# Connectors.net
KiCad netlist of a schematic drawn in Altium Designer
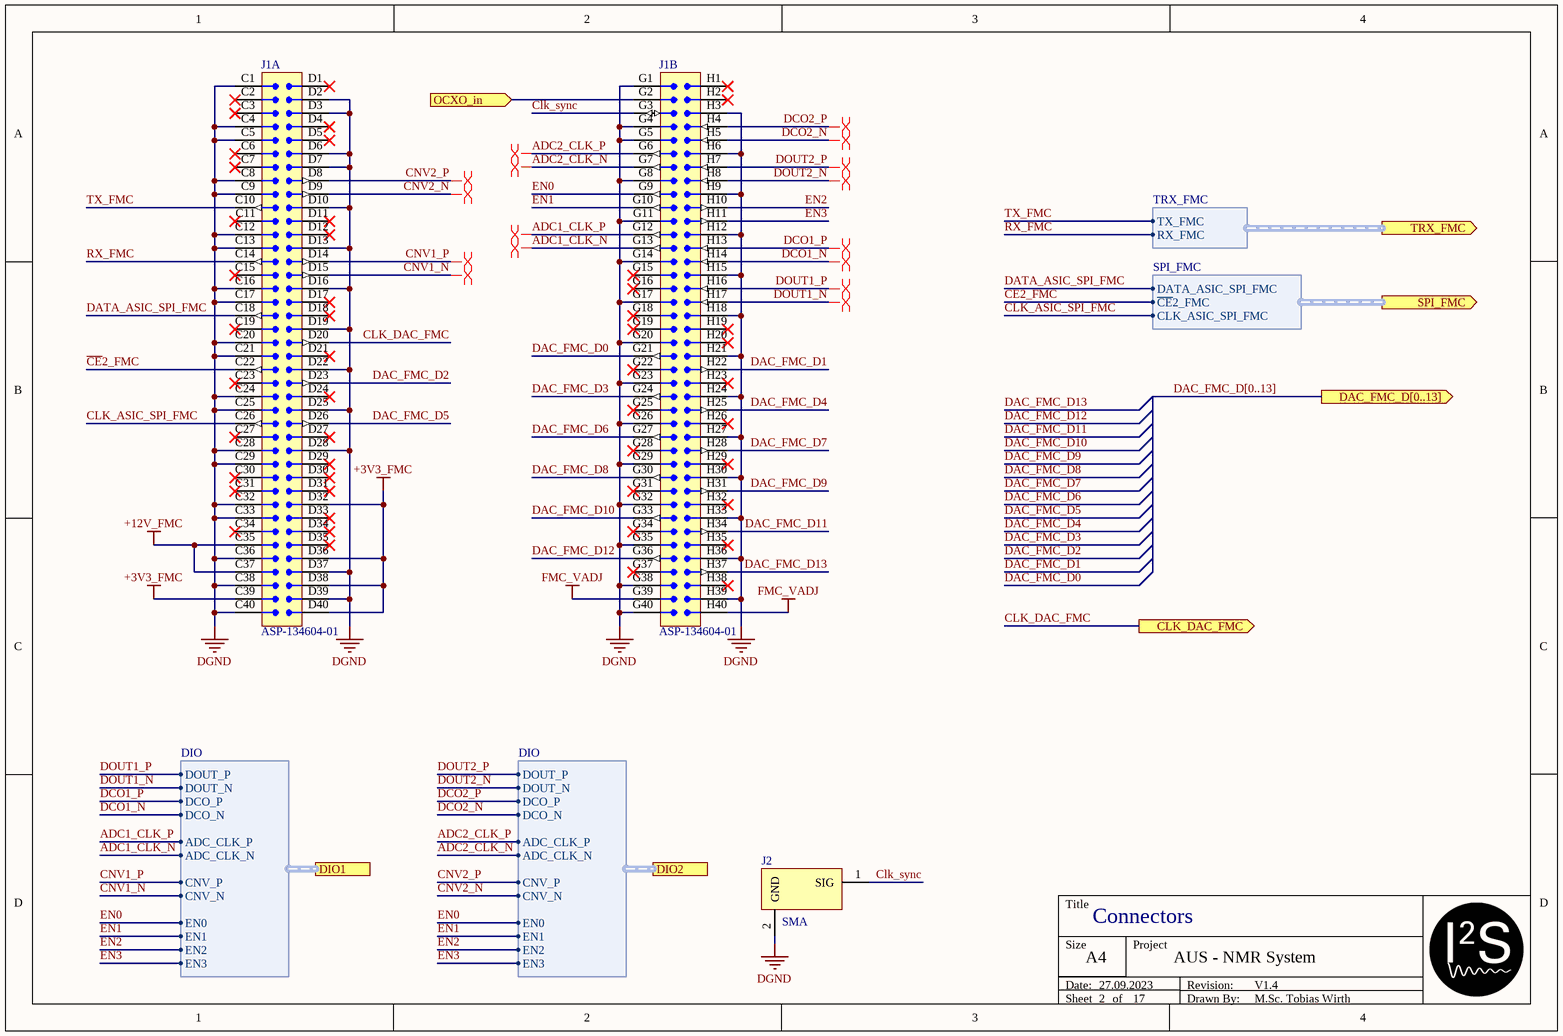
[diagram p0: Connectors.SchDoc]

(export (version "E")
  (design (tool "Eeschema 10.0.6"))
  (components
    (comp (ref "J1")
      (value "ASP-134604-01")
      (footprint "ASP13460401")
      (description "Board to Board & Mezzanine Connectors \"ASP\"")
      (libsource (lib "IIS-Lib_TW") (part "ASP-134604-01"))
    )
    (comp (ref "J2") (value "SMA") (footprint "SMA") (libsource (lib "IIS-Lib_TW") (part "SMA")))
  )
  (nets
    (net (code "4") (name "+3V3_FMC") (class "Default")
      (node (ref "J1") (pin "C39") (pinfunction "C39_C39") (pintype "passive"))
      (node (ref "J1") (pin "D32") (pinfunction "D32_D32") (pintype "passive"))
      (node (ref "J1") (pin "D36") (pinfunction "D36_D36") (pintype "passive"))
      (node (ref "J1") (pin "D38") (pinfunction "D38_D38") (pintype "passive"))
      (node (ref "J1") (pin "D40") (pinfunction "D40_D40") (pintype "passive"))
    )
    (net (code "5") (name "+12V_FMC") (class "Default")
      (node (ref "J1") (pin "C35") (pinfunction "C35_C35") (pintype "passive"))
      (node (ref "J1") (pin "C37") (pinfunction "C37_C37") (pintype "passive"))
    )
    (net (code "6") (name "/ADC1_CLK_N") (class "Default")
      (node (ref "J1") (pin "G13") (pinfunction "G13_G13") (pintype "output"))
    )
    (net (code "7") (name "/ADC1_CLK_P") (class "Default")
      (node (ref "J1") (pin "G12") (pinfunction "G12_G12") (pintype "output"))
    )
    (net (code "8") (name "/ADC2_CLK_N") (class "Default")
      (node (ref "J1") (pin "G7") (pinfunction "G7_G7") (pintype "output"))
    )
    (net (code "9") (name "/ADC2_CLK_P") (class "Default")
      (node (ref "J1") (pin "G6") (pinfunction "G6_G6") (pintype "output"))
    )
    (net (code "10") (name "/CLK_ASIC_SPI_FMC") (class "Default")
      (node (ref "J1") (pin "C26") (pinfunction "C26_C26") (pintype "passive"))
    )
    (net (code "11") (name "/CLK_DAC_FMC") (class "Default")
      (node (ref "J1") (pin "D20") (pinfunction "D20_D20") (pintype "passive"))
    )
    (net (code "12") (name "/CNV1_N") (class "Default")
      (node (ref "J1") (pin "D15") (pinfunction "D15_D15") (pintype "passive"))
    )
    (net (code "13") (name "/CNV1_P") (class "Default")
      (node (ref "J1") (pin "D14") (pinfunction "D14_D14") (pintype "passive"))
    )
    (net (code "14") (name "/CNV2_N") (class "Default")
      (node (ref "J1") (pin "D9") (pinfunction "D9_D9") (pintype "passive"))
    )
    (net (code "15") (name "/CNV2_P") (class "Default")
      (node (ref "J1") (pin "D8") (pinfunction "D8_D8") (pintype "passive"))
    )
    (net (code "16") (name "/Clk_sync") (class "Default")
      (node (ref "J1") (pin "G3") (pinfunction "G3_G3") (pintype "bidirectional"))
      (node (ref "J2") (pin "1") (pinfunction "SIG_1") (pintype "passive"))
    )
    (net (code "17") (name "/DAC_FMC_D0") (class "Default")
      (node (ref "J1") (pin "G21") (pinfunction "G21_G21") (pintype "output"))
    )
    (net (code "18") (name "/DAC_FMC_D1") (class "Default")
      (node (ref "J1") (pin "H22") (pinfunction "H22_H22") (pintype "output"))
    )
    (net (code "19") (name "/DAC_FMC_D2") (class "Default")
      (node (ref "J1") (pin "D23") (pinfunction "D23_D23") (pintype "passive"))
    )
    (net (code "20") (name "/DAC_FMC_D3") (class "Default")
      (node (ref "J1") (pin "G24") (pinfunction "G24_G24") (pintype "output"))
    )
    (net (code "21") (name "/DAC_FMC_D4") (class "Default")
      (node (ref "J1") (pin "H25") (pinfunction "H25_H25") (pintype "output"))
    )
    (net (code "22") (name "/DAC_FMC_D5") (class "Default")
      (node (ref "J1") (pin "D26") (pinfunction "D26_D26") (pintype "passive"))
    )
    (net (code "23") (name "/DAC_FMC_D6") (class "Default")
      (node (ref "J1") (pin "G27") (pinfunction "G27_G27") (pintype "output"))
    )
    (net (code "24") (name "/DAC_FMC_D7") (class "Default")
      (node (ref "J1") (pin "H28") (pinfunction "H28_H28") (pintype "output"))
    )
    (net (code "25") (name "/DAC_FMC_D8") (class "Default")
      (node (ref "J1") (pin "G30") (pinfunction "G30_G30") (pintype "output"))
    )
    (net (code "26") (name "/DAC_FMC_D9") (class "Default")
      (node (ref "J1") (pin "H31") (pinfunction "H31_H31") (pintype "output"))
    )
    (net (code "27") (name "/DAC_FMC_D10") (class "Default")
      (node (ref "J1") (pin "G33") (pinfunction "G33_G33") (pintype "output"))
    )
    (net (code "28") (name "/DAC_FMC_D11") (class "Default")
      (node (ref "J1") (pin "H34") (pinfunction "H34_H34") (pintype "output"))
    )
    (net (code "29") (name "/DAC_FMC_D12") (class "Default")
      (node (ref "J1") (pin "G36") (pinfunction "G36_G36") (pintype "output"))
    )
    (net (code "30") (name "/DAC_FMC_D13") (class "Default")
      (node (ref "J1") (pin "H37") (pinfunction "H37_H37") (pintype "output"))
    )
    (net (code "32") (name "/DATA_ASIC_SPI_FMC") (class "Default")
      (node (ref "J1") (pin "C18") (pinfunction "C18_C18") (pintype "passive"))
    )
    (net (code "33") (name "/DCO1_N") (class "Default")
      (node (ref "J1") (pin "H14") (pinfunction "H14_H14") (pintype "input"))
    )
    (net (code "34") (name "/DCO1_P") (class "Default")
      (node (ref "J1") (pin "H13") (pinfunction "H13_H13") (pintype "input"))
    )
    (net (code "35") (name "/DCO2_N") (class "Default")
      (node (ref "J1") (pin "H5") (pinfunction "H5_H5") (pintype "input"))
    )
    (net (code "36") (name "/DCO2_P") (class "Default")
      (node (ref "J1") (pin "H4") (pinfunction "H4_H4") (pintype "input"))
    )
    (net (code "37") (name "/DOUT1_N") (class "Default")
      (node (ref "J1") (pin "H17") (pinfunction "H17_H17") (pintype "input"))
    )
    (net (code "38") (name "/DOUT1_P") (class "Default")
      (node (ref "J1") (pin "H16") (pinfunction "H16_H16") (pintype "input"))
    )
    (net (code "39") (name "/DOUT2_N") (class "Default")
      (node (ref "J1") (pin "H8") (pinfunction "H8_H8") (pintype "input"))
    )
    (net (code "40") (name "/DOUT2_P") (class "Default")
      (node (ref "J1") (pin "H7") (pinfunction "H7_H7") (pintype "input"))
    )
    (net (code "41") (name "/EN0") (class "Default")
      (node (ref "J1") (pin "G9") (pinfunction "G9_G9") (pintype "output"))
    )
    (net (code "42") (name "/EN1") (class "Default")
      (node (ref "J1") (pin "G10") (pinfunction "G10_G10") (pintype "output"))
    )
    (net (code "43") (name "/EN2") (class "Default")
      (node (ref "J1") (pin "H10") (pinfunction "H10_H10") (pintype "output"))
    )
    (net (code "44") (name "/EN3") (class "Default")
      (node (ref "J1") (pin "H11") (pinfunction "H11_H11") (pintype "output"))
    )
    (net (code "45") (name "/OCXO_in") (class "Default")
      (node (ref "J1") (pin "G2") (pinfunction "G2_G2") (pintype "passive"))
    )
    (net (code "46") (name "/RX_FMC") (class "Default")
      (node (ref "J1") (pin "C14") (pinfunction "C14_C14") (pintype "passive"))
    )
    (net (code "47") (name "/TX_FMC") (class "Default")
      (node (ref "J1") (pin "C10") (pinfunction "C10_C10") (pintype "passive"))
    )
    (net (code "51") (name "/~{CE}2_FMC") (class "Default")
      (node (ref "J1") (pin "C22") (pinfunction "C22_C22") (pintype "passive"))
    )
    (net (code "52") (name "DGND") (class "Default")
      (node (ref "J1") (pin "C1") (pinfunction "C1_C1") (pintype "passive"))
      (node (ref "J1") (pin "C12") (pinfunction "C12_C12") (pintype "passive"))
      (node (ref "J1") (pin "C13") (pinfunction "C13_C13") (pintype "passive"))
      (node (ref "J1") (pin "C16") (pinfunction "C16_C16") (pintype "passive"))
      (node (ref "J1") (pin "C17") (pinfunction "C17_C17") (pintype "passive"))
      (node (ref "J1") (pin "C20") (pinfunction "C20_C20") (pintype "passive"))
      (node (ref "J1") (pin "C21") (pinfunction "C21_C21") (pintype "passive"))
      (node (ref "J1") (pin "C24") (pinfunction "C24_C24") (pintype "passive"))
      (node (ref "J1") (pin "C25") (pinfunction "C25_C25") (pintype "passive"))
      (node (ref "J1") (pin "C28") (pinfunction "C28_C28") (pintype "passive"))
      (node (ref "J1") (pin "C29") (pinfunction "C29_C29") (pintype "passive"))
      (node (ref "J1") (pin "C32") (pinfunction "C32_C32") (pintype "passive"))
      (node (ref "J1") (pin "C33") (pinfunction "C33_C33") (pintype "passive"))
      (node (ref "J1") (pin "C36") (pinfunction "C36_C36") (pintype "passive"))
      (node (ref "J1") (pin "C38") (pinfunction "C38_C38") (pintype "passive"))
      (node (ref "J1") (pin "C4") (pinfunction "C4_C4") (pintype "passive"))
      (node (ref "J1") (pin "C40") (pinfunction "C40_C40") (pintype "passive"))
      (node (ref "J1") (pin "C5") (pinfunction "C5_C5") (pintype "passive"))
      (node (ref "J1") (pin "C8") (pinfunction "C8_C8") (pintype "passive"))
      (node (ref "J1") (pin "C9") (pinfunction "C9_C9") (pintype "passive"))
      (node (ref "J1") (pin "D10") (pinfunction "D10_D10") (pintype "passive"))
      (node (ref "J1") (pin "D13") (pinfunction "D13_D13") (pintype "passive"))
      (node (ref "J1") (pin "D16") (pinfunction "D16_D16") (pintype "passive"))
      (node (ref "J1") (pin "D19") (pinfunction "D19_D19") (pintype "passive"))
      (node (ref "J1") (pin "D2") (pinfunction "D2_D2") (pintype "passive"))
      (node (ref "J1") (pin "D22") (pinfunction "D22_D22") (pintype "passive"))
      (node (ref "J1") (pin "D25") (pinfunction "D25_D25") (pintype "passive"))
      (node (ref "J1") (pin "D28") (pinfunction "D28_D28") (pintype "passive"))
      (node (ref "J1") (pin "D3") (pinfunction "D3_D3") (pintype "passive"))
      (node (ref "J1") (pin "D37") (pinfunction "D37_D37") (pintype "passive"))
      (node (ref "J1") (pin "D39") (pinfunction "D39_D39") (pintype "passive"))
      (node (ref "J1") (pin "D6") (pinfunction "D6_D6") (pintype "passive"))
      (node (ref "J1") (pin "D7") (pinfunction "D7_D7") (pintype "passive"))
      (node (ref "J1") (pin "G1") (pinfunction "G1_G1") (pintype "power_in"))
      (node (ref "J1") (pin "G11") (pinfunction "G11_G11") (pintype "power_in"))
      (node (ref "J1") (pin "G14") (pinfunction "G14_G14") (pintype "power_in"))
      (node (ref "J1") (pin "G17") (pinfunction "G17_G17") (pintype "power_in"))
      (node (ref "J1") (pin "G20") (pinfunction "G20_G20") (pintype "power_in"))
      (node (ref "J1") (pin "G23") (pinfunction "G23_G23") (pintype "power_in"))
      (node (ref "J1") (pin "G26") (pinfunction "G26_G26") (pintype "power_in"))
      (node (ref "J1") (pin "G29") (pinfunction "G29_G29") (pintype "power_in"))
      (node (ref "J1") (pin "G32") (pinfunction "G32_G32") (pintype "power_in"))
      (node (ref "J1") (pin "G35") (pinfunction "G35_G35") (pintype "power_in"))
      (node (ref "J1") (pin "G38") (pinfunction "G38_G38") (pintype "power_in"))
      (node (ref "J1") (pin "G4") (pinfunction "G4_G4") (pintype "power_in"))
      (node (ref "J1") (pin "G40") (pinfunction "G40_G40") (pintype "power_in"))
      (node (ref "J1") (pin "G5") (pinfunction "G5_G5") (pintype "power_in"))
      (node (ref "J1") (pin "G8") (pinfunction "G8_G8") (pintype "power_in"))
      (node (ref "J1") (pin "H12") (pinfunction "H12_H12") (pintype "power_in"))
      (node (ref "J1") (pin "H15") (pinfunction "H15_H15") (pintype "power_in"))
      (node (ref "J1") (pin "H18") (pinfunction "H18_H18") (pintype "power_in"))
      (node (ref "J1") (pin "H21") (pinfunction "H21_H21") (pintype "power_in"))
      (node (ref "J1") (pin "H24") (pinfunction "H24_H24") (pintype "power_in"))
      (node (ref "J1") (pin "H27") (pinfunction "H27_H27") (pintype "power_in"))
      (node (ref "J1") (pin "H3") (pinfunction "H3_H3") (pintype "power_in"))
      (node (ref "J1") (pin "H30") (pinfunction "H30_H30") (pintype "power_in"))
      (node (ref "J1") (pin "H33") (pinfunction "H33_H33") (pintype "power_in"))
      (node (ref "J1") (pin "H36") (pinfunction "H36_H36") (pintype "power_in"))
      (node (ref "J1") (pin "H39") (pinfunction "H39_H39") (pintype "power_in"))
      (node (ref "J1") (pin "H6") (pinfunction "H6_H6") (pintype "power_in"))
      (node (ref "J1") (pin "H9") (pinfunction "H9_H9") (pintype "power_in"))
      (node (ref "J2") (pin "2") (pinfunction "GND_2") (pintype "passive"))
    )
    (net (code "53") (name "FMC_VADJ") (class "Default")
      (node (ref "J1") (pin "G39") (pinfunction "G39_G39") (pintype "power_in"))
      (node (ref "J1") (pin "H40") (pinfunction "H40_H40") (pintype "power_in"))
    )
    (net (code "54") (name "unconnected-(J1-PadC2)") (class "Default")
      (node (ref "J1") (pin "C2") (pinfunction "C2_C2") (pintype "passive+no_connect"))
    )
    (net (code "55") (name "unconnected-(J1-PadC3)") (class "Default")
      (node (ref "J1") (pin "C3") (pinfunction "C3_C3") (pintype "passive+no_connect"))
    )
    (net (code "56") (name "unconnected-(J1-PadC6)") (class "Default")
      (node (ref "J1") (pin "C6") (pinfunction "C6_C6") (pintype "passive+no_connect"))
    )
    (net (code "57") (name "unconnected-(J1-PadC7)") (class "Default")
      (node (ref "J1") (pin "C7") (pinfunction "C7_C7") (pintype "passive+no_connect"))
    )
    (net (code "58") (name "unconnected-(J1-PadC11)") (class "Default")
      (node (ref "J1") (pin "C11") (pinfunction "C11_C11") (pintype "passive+no_connect"))
    )
    (net (code "59") (name "unconnected-(J1-PadC15)") (class "Default")
      (node (ref "J1") (pin "C15") (pinfunction "C15_C15") (pintype "passive+no_connect"))
    )
    (net (code "60") (name "unconnected-(J1-PadC19)") (class "Default")
      (node (ref "J1") (pin "C19") (pinfunction "C19_C19") (pintype "passive+no_connect"))
    )
    (net (code "61") (name "unconnected-(J1-PadC23)") (class "Default")
      (node (ref "J1") (pin "C23") (pinfunction "C23_C23") (pintype "passive+no_connect"))
    )
    (net (code "62") (name "unconnected-(J1-PadC27)") (class "Default")
      (node (ref "J1") (pin "C27") (pinfunction "C27_C27") (pintype "passive+no_connect"))
    )
    (net (code "63") (name "unconnected-(J1-PadC30)") (class "Default")
      (node (ref "J1") (pin "C30") (pinfunction "C30_C30") (pintype "passive+no_connect"))
    )
    (net (code "64") (name "unconnected-(J1-PadC31)") (class "Default")
      (node (ref "J1") (pin "C31") (pinfunction "C31_C31") (pintype "passive+no_connect"))
    )
    (net (code "65") (name "unconnected-(J1-PadC34)") (class "Default")
      (node (ref "J1") (pin "C34") (pinfunction "C34_C34") (pintype "passive+no_connect"))
    )
    (net (code "66") (name "unconnected-(J1-PadD1)") (class "Default")
      (node (ref "J1") (pin "D1") (pinfunction "D1_D1") (pintype "passive+no_connect"))
    )
    (net (code "67") (name "unconnected-(J1-PadD4)") (class "Default")
      (node (ref "J1") (pin "D4") (pinfunction "D4_D4") (pintype "passive+no_connect"))
    )
    (net (code "68") (name "unconnected-(J1-PadD5)") (class "Default")
      (node (ref "J1") (pin "D5") (pinfunction "D5_D5") (pintype "passive+no_connect"))
    )
    (net (code "69") (name "unconnected-(J1-PadD11)") (class "Default")
      (node (ref "J1") (pin "D11") (pinfunction "D11_D11") (pintype "passive+no_connect"))
    )
    (net (code "70") (name "unconnected-(J1-PadD12)") (class "Default")
      (node (ref "J1") (pin "D12") (pinfunction "D12_D12") (pintype "passive+no_connect"))
    )
    (net (code "71") (name "unconnected-(J1-PadD17)") (class "Default")
      (node (ref "J1") (pin "D17") (pinfunction "D17_D17") (pintype "passive+no_connect"))
    )
    (net (code "72") (name "unconnected-(J1-PadD18)") (class "Default")
      (node (ref "J1") (pin "D18") (pinfunction "D18_D18") (pintype "passive+no_connect"))
    )
    (net (code "73") (name "unconnected-(J1-PadD21)") (class "Default")
      (node (ref "J1") (pin "D21") (pinfunction "D21_D21") (pintype "passive+no_connect"))
    )
    (net (code "74") (name "unconnected-(J1-PadD24)") (class "Default")
      (node (ref "J1") (pin "D24") (pinfunction "D24_D24") (pintype "passive+no_connect"))
    )
    (net (code "75") (name "unconnected-(J1-PadD27)") (class "Default")
      (node (ref "J1") (pin "D27") (pinfunction "D27_D27") (pintype "passive+no_connect"))
    )
    (net (code "76") (name "unconnected-(J1-PadD29)") (class "Default")
      (node (ref "J1") (pin "D29") (pinfunction "D29_D29") (pintype "passive+no_connect"))
    )
    (net (code "77") (name "unconnected-(J1-PadD30)") (class "Default")
      (node (ref "J1") (pin "D30") (pinfunction "D30_D30") (pintype "passive+no_connect"))
    )
    (net (code "78") (name "unconnected-(J1-PadD31)") (class "Default")
      (node (ref "J1") (pin "D31") (pinfunction "D31_D31") (pintype "passive+no_connect"))
    )
    (net (code "79") (name "unconnected-(J1-PadD33)") (class "Default")
      (node (ref "J1") (pin "D33") (pinfunction "D33_D33") (pintype "passive+no_connect"))
    )
    (net (code "80") (name "unconnected-(J1-PadD34)") (class "Default")
      (node (ref "J1") (pin "D34") (pinfunction "D34_D34") (pintype "passive+no_connect"))
    )
    (net (code "81") (name "unconnected-(J1-PadD35)") (class "Default")
      (node (ref "J1") (pin "D35") (pinfunction "D35_D35") (pintype "passive+no_connect"))
    )
    (net (code "82") (name "unconnected-(J1-PadG15)") (class "Default")
      (node (ref "J1") (pin "G15") (pinfunction "G15_G15") (pintype "passive+no_connect"))
    )
    (net (code "83") (name "unconnected-(J1-PadG16)") (class "Default")
      (node (ref "J1") (pin "G16") (pinfunction "G16_G16") (pintype "passive+no_connect"))
    )
    (net (code "84") (name "unconnected-(J1-PadG18)") (class "Default")
      (node (ref "J1") (pin "G18") (pinfunction "G18_G18") (pintype "passive+no_connect"))
    )
    (net (code "85") (name "unconnected-(J1-PadG19)") (class "Default")
      (node (ref "J1") (pin "G19") (pinfunction "G19_G19") (pintype "passive+no_connect"))
    )
    (net (code "86") (name "unconnected-(J1-PadG22)") (class "Default")
      (node (ref "J1") (pin "G22") (pinfunction "G22_G22") (pintype "passive+no_connect"))
    )
    (net (code "87") (name "unconnected-(J1-PadG25)") (class "Default")
      (node (ref "J1") (pin "G25") (pinfunction "G25_G25") (pintype "passive+no_connect"))
    )
    (net (code "88") (name "unconnected-(J1-PadG28)") (class "Default")
      (node (ref "J1") (pin "G28") (pinfunction "G28_G28") (pintype "passive+no_connect"))
    )
    (net (code "89") (name "unconnected-(J1-PadG31)") (class "Default")
      (node (ref "J1") (pin "G31") (pinfunction "G31_G31") (pintype "passive+no_connect"))
    )
    (net (code "90") (name "unconnected-(J1-PadG34)") (class "Default")
      (node (ref "J1") (pin "G34") (pinfunction "G34_G34") (pintype "passive+no_connect"))
    )
    (net (code "91") (name "unconnected-(J1-PadG37)") (class "Default")
      (node (ref "J1") (pin "G37") (pinfunction "G37_G37") (pintype "passive+no_connect"))
    )
    (net (code "92") (name "unconnected-(J1-PadH1)") (class "Default")
      (node (ref "J1") (pin "H1") (pinfunction "H1_H1") (pintype "passive+no_connect"))
    )
    (net (code "93") (name "unconnected-(J1-PadH2)") (class "Default")
      (node (ref "J1") (pin "H2") (pinfunction "H2_H2") (pintype "passive+no_connect"))
    )
    (net (code "94") (name "unconnected-(J1-PadH19)") (class "Default")
      (node (ref "J1") (pin "H19") (pinfunction "H19_H19") (pintype "passive+no_connect"))
    )
    (net (code "95") (name "unconnected-(J1-PadH20)") (class "Default")
      (node (ref "J1") (pin "H20") (pinfunction "H20_H20") (pintype "passive+no_connect"))
    )
    (net (code "96") (name "unconnected-(J1-PadH23)") (class "Default")
      (node (ref "J1") (pin "H23") (pinfunction "H23_H23") (pintype "passive+no_connect"))
    )
    (net (code "97") (name "unconnected-(J1-PadH26)") (class "Default")
      (node (ref "J1") (pin "H26") (pinfunction "H26_H26") (pintype "passive+no_connect"))
    )
    (net (code "98") (name "unconnected-(J1-PadH29)") (class "Default")
      (node (ref "J1") (pin "H29") (pinfunction "H29_H29") (pintype "passive+no_connect"))
    )
    (net (code "99") (name "unconnected-(J1-PadH32)") (class "Default")
      (node (ref "J1") (pin "H32") (pinfunction "H32_H32") (pintype "passive+no_connect"))
    )
    (net (code "100") (name "unconnected-(J1-PadH35)") (class "Default")
      (node (ref "J1") (pin "H35") (pinfunction "H35_H35") (pintype "passive+no_connect"))
    )
    (net (code "101") (name "unconnected-(J1-PadH38)") (class "Default")
      (node (ref "J1") (pin "H38") (pinfunction "H38_H38") (pintype "passive+no_connect"))
    )
  )
)
